# Power.net
KiCad netlist of a schematic drawn in Altium Designer
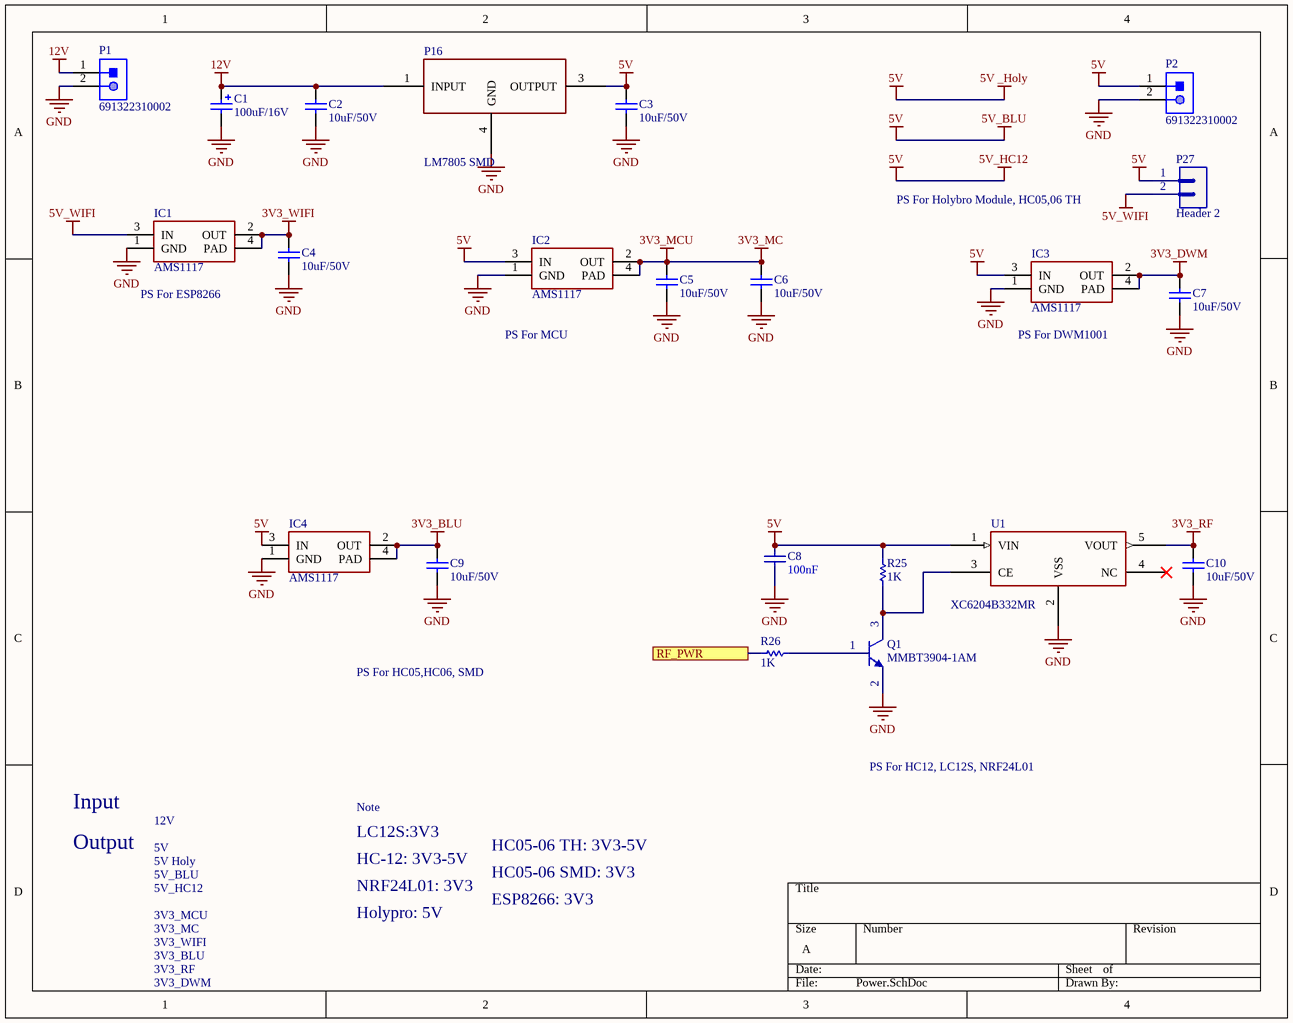
[diagram p0: Power.SchDoc]

(export (version "E")
  (design (tool "Eeschema 10.0.6"))
  (components
    (comp (ref "C1")
      (value "100uF/16V")
      (footprint "CAP_SM_TAN")
      (fields
        (field (name "MANUFACTURER") "Nichicon")
        (field (name "MANUFACTURER PART NUMBER") "UWX1C101MCL1GB")
        (field (name "Comment") "TAJB107M006RNJ")
      )
      (libsource (lib "Capacitor") (part "Cap-Tan-100uF-16V"))
    )
    (comp (ref "C2")
      (value "10uF/50V")
      (footprint "CAP-SM-0805")
      (description "CAP CER 10UF 50V X5R 0805")
      (fields
        (field (name "MANUFACTURER") "Yageo")
        (field (name "MANUFACTURER PART NUMBER") "CC0805KKX5R9BB106")
      )
      (libsource (lib "Capacitor") (part "Cap-10uF-50V-0805"))
    )
    (comp (ref "C3")
      (value "10uF/50V")
      (footprint "CAP-SM-0805")
      (description "CAP CER 10UF 50V X5R 0805")
      (fields
        (field (name "MANUFACTURER") "Yageo")
        (field (name "MANUFACTURER PART NUMBER") "CC0805KKX5R9BB106")
      )
      (libsource (lib "Capacitor") (part "Cap-10uF-50V-0805"))
    )
    (comp (ref "C4")
      (value "10uF/50V")
      (footprint "CAP-SM-0805")
      (description "CAP CER 10UF 50V X5R 0805")
      (fields
        (field (name "MANUFACTURER") "Yageo")
        (field (name "MANUFACTURER PART NUMBER") "CC0805KKX5R9BB106")
      )
      (libsource (lib "Capacitor") (part "Cap-10uF-50V-0805"))
    )
    (comp (ref "C5")
      (value "10uF/50V")
      (footprint "CAP-SM-0805")
      (description "CAP CER 10UF 50V X5R 0805")
      (fields
        (field (name "MANUFACTURER") "Yageo")
        (field (name "MANUFACTURER PART NUMBER") "CC0805KKX5R9BB106")
      )
      (libsource (lib "Capacitor") (part "Cap-10uF-50V-0805"))
    )
    (comp (ref "C6")
      (value "10uF/50V")
      (footprint "CAP-SM-0805")
      (description "CAP CER 10UF 50V X5R 0805")
      (fields
        (field (name "MANUFACTURER") "Yageo")
        (field (name "MANUFACTURER PART NUMBER") "CC0805KKX5R9BB106")
      )
      (libsource (lib "Capacitor") (part "Cap-10uF-50V-0805"))
    )
    (comp (ref "C7")
      (value "10uF/50V")
      (footprint "CAP-SM-0805")
      (description "CAP CER 10UF 50V X5R 0805")
      (fields
        (field (name "MANUFACTURER") "Yageo")
        (field (name "MANUFACTURER PART NUMBER") "CC0805KKX5R9BB106")
      )
      (libsource (lib "Capacitor") (part "Cap-10uF-50V-0805"))
    )
    (comp (ref "C8")
      (value "100nF")
      (footprint "CAP-SM-0805")
      (description "Capacitor")
      (fields (field (name "Comment") "Cap Non-Pol SMD"))
      (libsource (lib "PIF_C16_lib (1)") (part "Cap Non-Pol SMD"))
    )
    (comp (ref "C9")
      (value "10uF/50V")
      (footprint "CAP-SM-0805")
      (description "CAP CER 10UF 50V X5R 0805")
      (fields
        (field (name "MANUFACTURER") "Yageo")
        (field (name "MANUFACTURER PART NUMBER") "CC0805KKX5R9BB106")
      )
      (libsource (lib "Capacitor") (part "Cap-10uF-50V-0805"))
    )
    (comp (ref "C10")
      (value "10uF/50V")
      (footprint "CAP-SM-0805")
      (description "CAP CER 10UF 50V X5R 0805")
      (fields
        (field (name "MANUFACTURER") "Yageo")
        (field (name "MANUFACTURER PART NUMBER") "CC0805KKX5R9BB106")
      )
      (libsource (lib "Capacitor") (part "Cap-10uF-50V-0805"))
    )
    (comp (ref "IC1")
      (value "AMS1117")
      (footprint "SOT223")
      (description "Available in 1.8V, 2.5V, 2.85V, 3.3V, 5V, and  Adjustable Versions")
      (libsource (lib "PI") (part "AMS1117"))
    )
    (comp (ref "IC2")
      (value "AMS1117")
      (footprint "SOT223")
      (description "Available in 1.8V, 2.5V, 2.85V, 3.3V, 5V, and  Adjustable Versions")
      (libsource (lib "PI") (part "AMS1117"))
    )
    (comp (ref "IC3")
      (value "AMS1117")
      (footprint "SOT223")
      (description "Available in 1.8V, 2.5V, 2.85V, 3.3V, 5V, and  Adjustable Versions")
      (libsource (lib "PI") (part "AMS1117"))
    )
    (comp (ref "IC4")
      (value "AMS1117")
      (footprint "SOT223")
      (description "Available in 1.8V, 2.5V, 2.85V, 3.3V, 5V, and  Adjustable Versions")
      (libsource (lib "PI") (part "AMS1117"))
    )
    (comp (ref "P1")
      (value "691322310002")
      (footprint "691322310002")
      (description "WR-TBL Serie 322 Horizontal PCB Header, Pluggable, pitch 3.81mm, 2p")
      (fields (field (name "PUBLISHER") "Wurth Elektronik"))
      (libsource (lib "o162719v243 Altium_WR-TBL (rev19a)") (part "691322310002"))
    )
    (comp (ref "P2")
      (value "691322310002")
      (footprint "691322310002")
      (description "WR-TBL Serie 322 Horizontal PCB Header, Pluggable, pitch 3.81mm, 2p")
      (fields (field (name "PUBLISHER") "Wurth Elektronik"))
      (libsource (lib "o162719v243 Altium_WR-TBL (rev19a)") (part "691322310002"))
    )
    (comp (ref "P16")
      (value "LM7805 SMD")
      (footprint "D2PAK_STM")
      (libsource (lib "PIF_robot") (part "LM7805 SMD"))
    )
    (comp (ref "P27")
      (value "Header 2")
      (footprint "JP2")
      (description "Header, 2-Pin")
      (fields (field (name "PUBLISHER") "Altium Limited"))
      (libsource (lib "PIF_C16_lib (1)") (part "Header 2"))
    )
    (comp (ref "Q1")
      (value "MMBT3904-1AM")
      (footprint "SOT23_NEX")
      (libsource (lib "BJT") (part "MMBT3904-1AM"))
    )
    (comp (ref "R25")
      (value "1K")
      (footprint "RES-SM-0805")
      (fields (field (name "Comment") "Resistor 1/4W"))
      (libsource (lib "PIF_C16_lib (1)") (part "RES"))
    )
    (comp (ref "R26")
      (value "1K")
      (footprint "RES-SM-0805")
      (fields (field (name "Comment") "Resistor 1/4W"))
      (libsource (lib "PIF_C16_lib (1)") (part "RES"))
    )
    (comp (ref "U1")
      (value "XC6204B332MR")
      (footprint "XC6204/05_SOT-00")
      (fields (field (name "COPYRIGHT") "Copyright (C) 2018 Accelerated Designs. All rights reserved"))
      (libsource (lib "PI") (part "XC6204B332MR"))
    )
  )
  (nets
    (net (code "1") (name "/RF_PWR") (class "Default") (node (ref "R26") (pin "1") (pintype "passive")))
    (net (code "2") (name "3V3_BLU") (class "Default")
      (node (ref "C9") (pin "2") (pinfunction "2_2") (pintype "passive"))
      (node (ref "IC4") (pin "2") (pinfunction "OUT_2") (pintype "passive"))
      (node (ref "IC4") (pin "4") (pinfunction "PAD_4") (pintype "passive"))
    )
    (net (code "3") (name "3V3_DWM") (class "Default")
      (node (ref "C7") (pin "2") (pinfunction "2_2") (pintype "passive"))
      (node (ref "IC3") (pin "2") (pinfunction "OUT_2") (pintype "passive"))
      (node (ref "IC3") (pin "4") (pinfunction "PAD_4") (pintype "passive"))
    )
    (net (code "4") (name "3V3_MC") (class "Default")
      (node (ref "C5") (pin "2") (pinfunction "2_2") (pintype "passive"))
      (node (ref "C6") (pin "2") (pinfunction "2_2") (pintype "passive"))
      (node (ref "IC2") (pin "2") (pinfunction "OUT_2") (pintype "passive"))
      (node (ref "IC2") (pin "4") (pinfunction "PAD_4") (pintype "passive"))
    )
    (net (code "5") (name "3V3_RF") (class "Default")
      (node (ref "C10") (pin "2") (pinfunction "2_2") (pintype "passive"))
      (node (ref "U1") (pin "5") (pinfunction "VOUT_5") (pintype "output"))
    )
    (net (code "6") (name "3V3_WIFI") (class "Default")
      (node (ref "C4") (pin "2") (pinfunction "2_2") (pintype "passive"))
      (node (ref "IC1") (pin "2") (pinfunction "OUT_2") (pintype "passive"))
      (node (ref "IC1") (pin "4") (pinfunction "PAD_4") (pintype "passive"))
    )
    (net (code "7") (name "5V") (class "Default")
      (node (ref "C3") (pin "2") (pinfunction "2_2") (pintype "passive"))
      (node (ref "C8") (pin "2") (pinfunction "2_2") (pintype "passive"))
      (node (ref "IC2") (pin "3") (pinfunction "IN_3") (pintype "passive"))
      (node (ref "IC3") (pin "3") (pinfunction "IN_3") (pintype "passive"))
      (node (ref "IC4") (pin "3") (pinfunction "IN_3") (pintype "passive"))
      (node (ref "P16") (pin "3") (pinfunction "OUTPUT_3") (pintype "passive"))
      (node (ref "P2") (pin "1") (pinfunction "1_1") (pintype "passive"))
      (node (ref "P27") (pin "1") (pinfunction "1_1") (pintype "passive"))
      (node (ref "R25") (pin "2") (pintype "passive"))
      (node (ref "U1") (pin "1") (pinfunction "VIN_1") (pintype "input"))
    )
    (net (code "8") (name "5V_WIFI") (class "Default")
      (node (ref "IC1") (pin "3") (pinfunction "IN_3") (pintype "passive"))
      (node (ref "P27") (pin "2") (pinfunction "2_2") (pintype "passive"))
    )
    (net (code "9") (name "12V") (class "Default")
      (node (ref "C1") (pin "1") (pinfunction "1_1") (pintype "passive"))
      (node (ref "C2") (pin "2") (pinfunction "2_2") (pintype "passive"))
      (node (ref "P1") (pin "1") (pinfunction "1_1") (pintype "passive"))
      (node (ref "P16") (pin "1") (pinfunction "INPUT_1") (pintype "passive"))
    )
    (net (code "10") (name "GND") (class "Default")
      (node (ref "C1") (pin "2") (pinfunction "2_2") (pintype "passive"))
      (node (ref "C10") (pin "1") (pinfunction "1_1") (pintype "passive"))
      (node (ref "C2") (pin "1") (pinfunction "1_1") (pintype "passive"))
      (node (ref "C3") (pin "1") (pinfunction "1_1") (pintype "passive"))
      (node (ref "C4") (pin "1") (pinfunction "1_1") (pintype "passive"))
      (node (ref "C5") (pin "1") (pinfunction "1_1") (pintype "passive"))
      (node (ref "C6") (pin "1") (pinfunction "1_1") (pintype "passive"))
      (node (ref "C7") (pin "1") (pinfunction "1_1") (pintype "passive"))
      (node (ref "C8") (pin "1") (pinfunction "1_1") (pintype "passive"))
      (node (ref "C9") (pin "1") (pinfunction "1_1") (pintype "passive"))
      (node (ref "IC1") (pin "1") (pinfunction "GND_1") (pintype "passive"))
      (node (ref "IC2") (pin "1") (pinfunction "GND_1") (pintype "passive"))
      (node (ref "IC3") (pin "1") (pinfunction "GND_1") (pintype "passive"))
      (node (ref "IC4") (pin "1") (pinfunction "GND_1") (pintype "passive"))
      (node (ref "P1") (pin "2") (pinfunction "2_2") (pintype "passive"))
      (node (ref "P16") (pin "4") (pinfunction "GND_4") (pintype "passive"))
      (node (ref "P2") (pin "2") (pinfunction "2_2") (pintype "passive"))
      (node (ref "Q1") (pin "2") (pinfunction "E_2") (pintype "passive"))
      (node (ref "U1") (pin "2") (pinfunction "VSS_2") (pintype "passive"))
    )
    (net (code "11") (name "Net-(Q1-B)") (class "Default")
      (node (ref "Q1") (pin "1") (pinfunction "B_1") (pintype "passive"))
      (node (ref "R26") (pin "2") (pintype "passive"))
    )
    (net (code "12") (name "Net-(Q1-C)") (class "Default")
      (node (ref "Q1") (pin "3") (pinfunction "C_3") (pintype "passive"))
      (node (ref "R25") (pin "1") (pintype "passive"))
      (node (ref "U1") (pin "3") (pinfunction "CE_3") (pintype "passive"))
    )
    (net (code "13") (name "unconnected-(U1-NC-Pad4)") (class "Default")
      (node (ref "U1") (pin "4") (pinfunction "NC_4") (pintype "passive+no_connect"))
    )
  )
)
